# shield.net
KiCad netlist of a schematic drawn in EAGLE
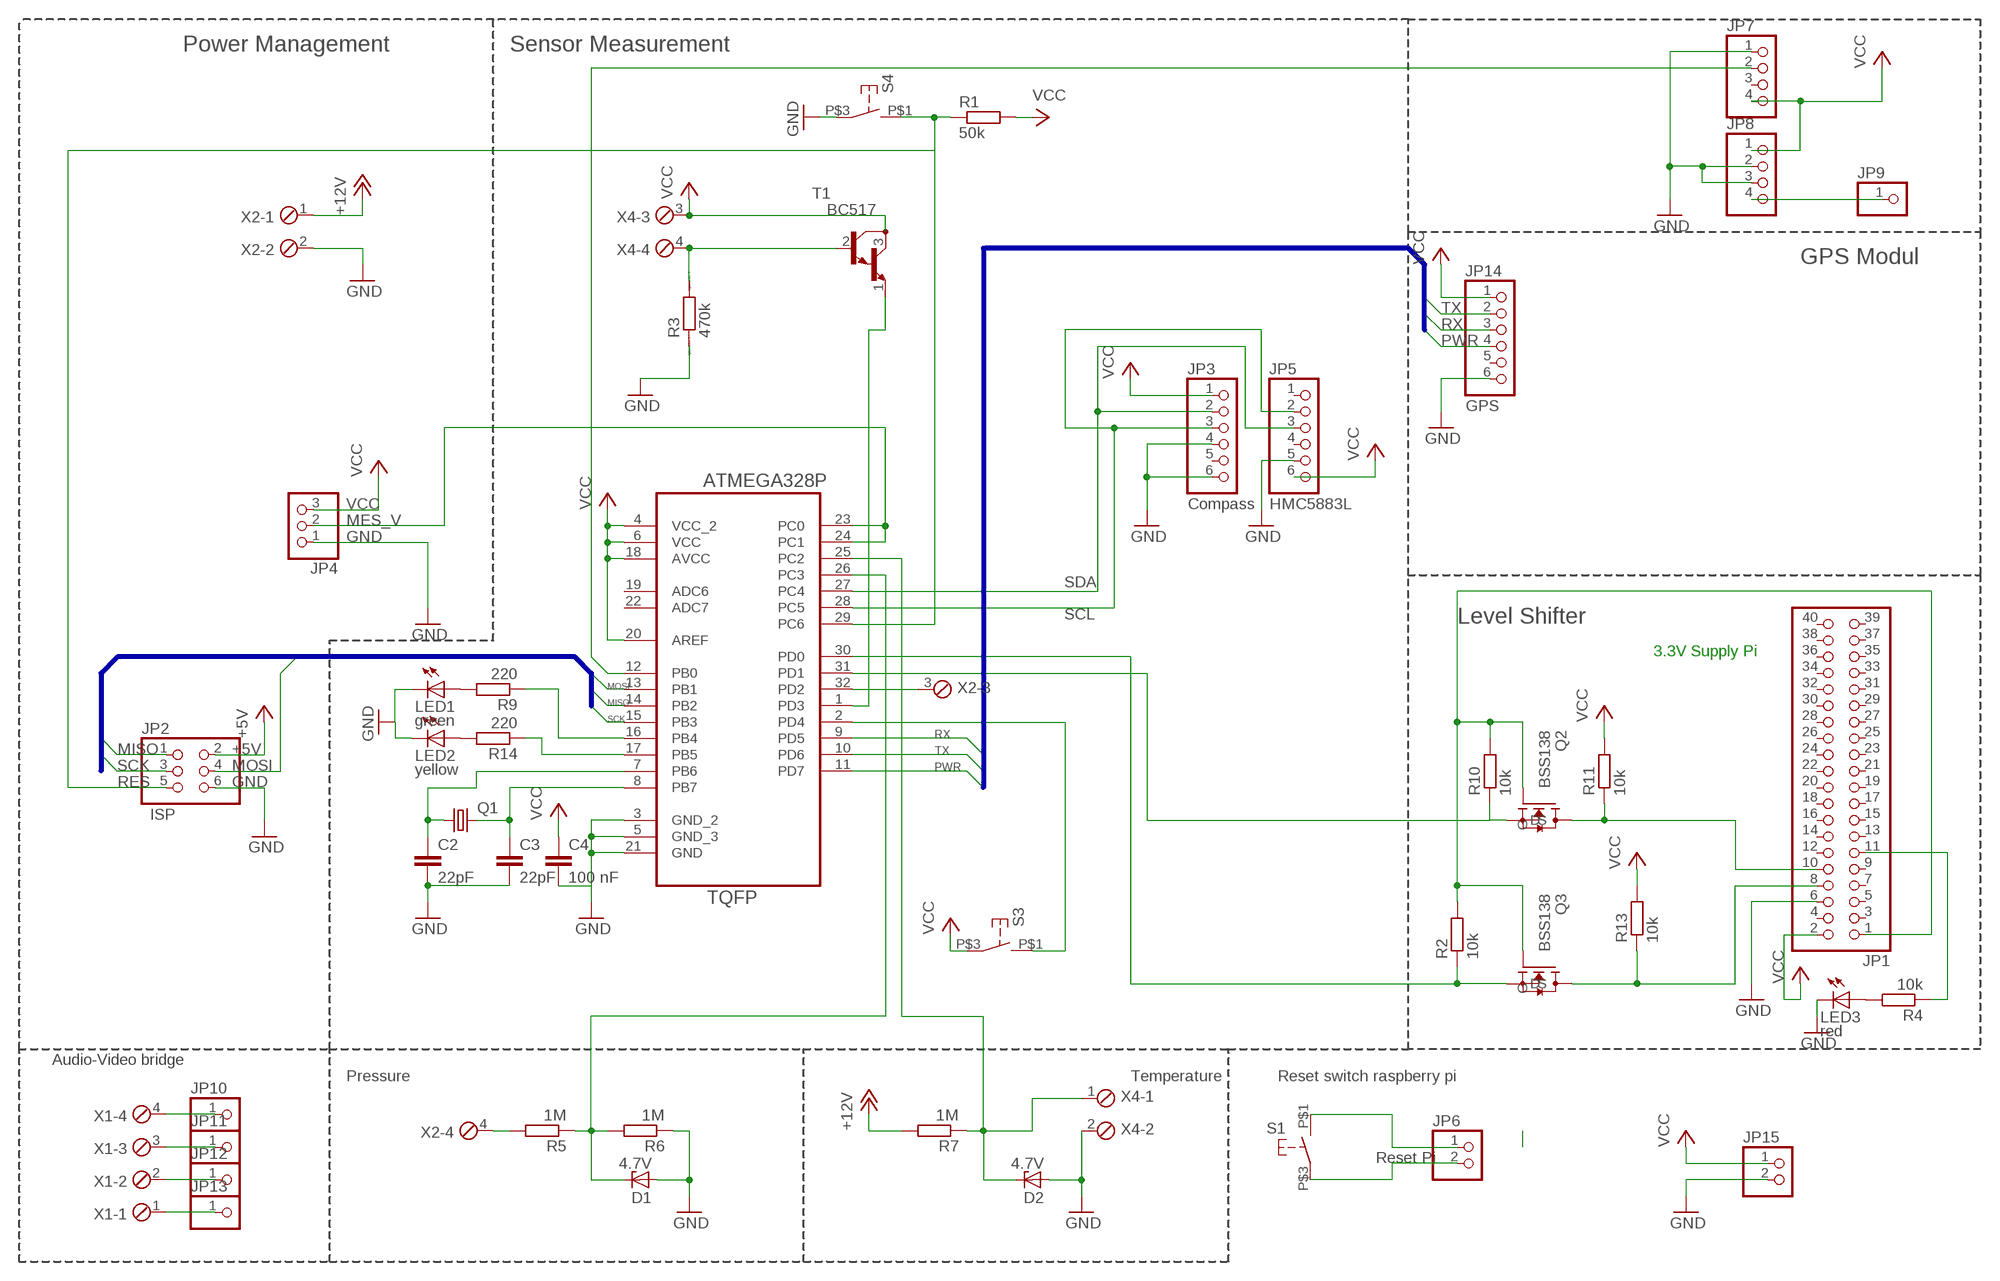
[diagram p0: schematic, sheet 1]

(export (version "E")
  (design (tool "Eeschema 10.0.6"))
  (components
    (comp (ref "C2")
      (value "22pF")
      (footprint "eagle-import:C1206")
      (libsource (lib "eagle-import") (part "C-EUC1206"))
    )
    (comp (ref "C3")
      (value "22pF")
      (footprint "eagle-import:C1206")
      (libsource (lib "eagle-import") (part "C-EUC1206"))
    )
    (comp (ref "C4")
      (value "100 nF")
      (footprint "eagle-import:C0603")
      (libsource (lib "eagle-import") (part "C-EUC0603"))
    )
    (comp (ref "D1")
      (value "4.7V")
      (footprint "eagle-import:SOT23")
      (libsource (lib "eagle-import") (part "ZENER-DIODESOT23"))
    )
    (comp (ref "D2")
      (value "4.7V")
      (footprint "eagle-import:SOT23")
      (libsource (lib "eagle-import") (part "ZENER-DIODESOT23"))
    )
    (comp (ref "IC1")
      (value "ATMEGA328P-AU")
      (footprint "eagle-import:QFP80P900X900X120-32N")
      (libsource (lib "eagle-import") (part "ATMEGA328P-AU"))
    )
    (comp (ref "JP1")
      (value "PINHD-2X20")
      (footprint "eagle-import:2X20")
      (libsource (lib "eagle-import") (part "PINHD-2X20"))
    )
    (comp (ref "JP2")
      (value "PINHD-2X3")
      (footprint "eagle-import:2X03")
      (libsource (lib "eagle-import") (part "PINHD-2X3"))
    )
    (comp (ref "JP3")
      (value "Compass")
      (footprint "eagle-import:1X06")
      (libsource (lib "eagle-import") (part "PINHD-1X6"))
    )
    (comp (ref "JP4")
      (value "PINHD-1X3")
      (footprint "eagle-import:1X03")
      (libsource (lib "eagle-import") (part "PINHD-1X3"))
    )
    (comp (ref "JP5")
      (value "HMC5883L")
      (footprint "eagle-import:1X06")
      (libsource (lib "eagle-import") (part "PINHD-1X6"))
    )
    (comp (ref "JP6")
      (value "PINHD-1X2")
      (footprint "eagle-import:1X02")
      (libsource (lib "eagle-import") (part "PINHD-1X2"))
    )
    (comp (ref "JP7")
      (value "PINHD-1X4")
      (footprint "eagle-import:1X04")
      (libsource (lib "eagle-import") (part "PINHD-1X4"))
    )
    (comp (ref "JP8")
      (value "PINHD-1X4")
      (footprint "eagle-import:1X04")
      (libsource (lib "eagle-import") (part "PINHD-1X4"))
    )
    (comp (ref "JP9")
      (value "PINHD-1X1")
      (footprint "eagle-import:1X01")
      (libsource (lib "eagle-import") (part "PINHD-1X1"))
    )
    (comp (ref "JP10")
      (value "PINHD-1X1")
      (footprint "eagle-import:1X01")
      (libsource (lib "eagle-import") (part "PINHD-1X1"))
    )
    (comp (ref "JP11")
      (value "PINHD-1X1")
      (footprint "eagle-import:1X01")
      (libsource (lib "eagle-import") (part "PINHD-1X1"))
    )
    (comp (ref "JP12")
      (value "PINHD-1X1")
      (footprint "eagle-import:1X01")
      (libsource (lib "eagle-import") (part "PINHD-1X1"))
    )
    (comp (ref "JP13")
      (value "PINHD-1X1")
      (footprint "eagle-import:1X01")
      (libsource (lib "eagle-import") (part "PINHD-1X1"))
    )
    (comp (ref "JP14")
      (value "GPS")
      (footprint "eagle-import:1X06")
      (libsource (lib "eagle-import") (part "PINHD-1X6"))
    )
    (comp (ref "JP15")
      (value "PINHD-1X2")
      (footprint "eagle-import:1X02")
      (libsource (lib "eagle-import") (part "PINHD-1X2"))
    )
    (comp (ref "LED1")
      (value "green")
      (footprint "eagle-import:LED3MM")
      (libsource (lib "eagle-import") (part "LED3MM"))
    )
    (comp (ref "LED2")
      (value "yellow")
      (footprint "eagle-import:LED3MM")
      (libsource (lib "eagle-import") (part "LED3MM"))
    )
    (comp (ref "LED3")
      (value "red")
      (footprint "eagle-import:LED3MM")
      (libsource (lib "eagle-import") (part "LED3MM"))
    )
    (comp (ref "Q1")
      (value "CRYSTALHC49UP")
      (footprint "eagle-import:HC49UP")
      (libsource (lib "eagle-import") (part "CRYSTALHC49UP"))
    )
    (comp (ref "Q2")
      (value "BSS138")
      (footprint "eagle-import:BSS138")
      (libsource (lib "eagle-import") (part "BSS138"))
    )
    (comp (ref "Q3")
      (value "BSS138")
      (footprint "eagle-import:BSS138")
      (libsource (lib "eagle-import") (part "BSS138"))
    )
    (comp (ref "R1")
      (value "50k")
      (footprint "eagle-import:R1206")
      (libsource (lib "eagle-import") (part "resistor_R-EU_R1206"))
    )
    (comp (ref "R2")
      (value "10k")
      (footprint "eagle-import:R1206")
      (libsource (lib "eagle-import") (part "resistor_R-EU_R1206"))
    )
    (comp (ref "R3")
      (value "470k")
      (footprint "eagle-import:R1206")
      (libsource (lib "eagle-import") (part "RR1206"))
    )
    (comp (ref "R4")
      (value "10k")
      (footprint "eagle-import:R1206")
      (libsource (lib "eagle-import") (part "resistor_R-EU_R1206"))
    )
    (comp (ref "R5")
      (value "1M")
      (footprint "eagle-import:R1206")
      (libsource (lib "eagle-import") (part "R-EU_R1206"))
    )
    (comp (ref "R6")
      (value "1M")
      (footprint "eagle-import:R1206")
      (libsource (lib "eagle-import") (part "R-EU_R1206"))
    )
    (comp (ref "R7")
      (value "1M")
      (footprint "eagle-import:R1206")
      (libsource (lib "eagle-import") (part "R-EU_R1206"))
    )
    (comp (ref "R9")
      (value "220")
      (footprint "eagle-import:R1206")
      (libsource (lib "eagle-import") (part "resistor_R-EU_R1206"))
    )
    (comp (ref "R10")
      (value "10k")
      (footprint "eagle-import:R1206")
      (libsource (lib "eagle-import") (part "resistor_R-EU_R1206"))
    )
    (comp (ref "R11")
      (value "10k")
      (footprint "eagle-import:R1206")
      (libsource (lib "eagle-import") (part "resistor_R-EU_R1206"))
    )
    (comp (ref "R13")
      (value "10k")
      (footprint "eagle-import:R1206")
      (libsource (lib "eagle-import") (part "resistor_R-EU_R1206"))
    )
    (comp (ref "R14")
      (value "220")
      (footprint "eagle-import:R1206")
      (libsource (lib "eagle-import") (part "resistor_R-EU_R1206"))
    )
    (comp (ref "S1")
      (value "SCHLIESSER_TASTSCHALTER")
      (footprint "eagle-import:NAMAE-JTP-1130")
      (libsource (lib "eagle-import") (part "SCHLIESSER_TASTSCHALTER"))
    )
    (comp (ref "S3")
      (value "SCHLIESSER_TASTSCHALTER")
      (footprint "eagle-import:NAMAE-JTP-1130")
      (libsource (lib "eagle-import") (part "SCHLIESSER_TASTSCHALTER"))
    )
    (comp (ref "S4")
      (value "SCHLIESSER_TASTSCHALTER")
      (footprint "eagle-import:NAMAE-JTP-1130")
      (libsource (lib "eagle-import") (part "SCHLIESSER_TASTSCHALTER"))
    )
    (comp (ref "T1")
      (value "BC517")
      (footprint "eagle-import:TO92")
      (libsource (lib "eagle-import") (part "BC517"))
    )
    (comp (ref "X1")
      (value "MPT4")
      (footprint "eagle-import:4POL254")
      (libsource (lib "eagle-import") (part "MPT4"))
    )
    (comp (ref "X2")
      (value "MPT4")
      (footprint "eagle-import:4POL254")
      (libsource (lib "eagle-import") (part "MPT4"))
    )
    (comp (ref "X4")
      (value "MPT4")
      (footprint "eagle-import:4POL254")
      (libsource (lib "eagle-import") (part "MPT4"))
    )
  )
  (nets
    (net (code "1") (name "+5V") (class "Default")
      (node (ref "JP2") (pin "2") (pinfunction "2_2") (pintype "passive"))
    )
    (net (code "2") (name "+12V") (class "Default")
      (node (ref "R7") (pin "2") (pinfunction "2_2") (pintype "passive"))
      (node (ref "X2") (pin "1") (pinfunction "1_1") (pintype "passive"))
    )
    (net (code "3") (name "/MES_V") (class "Default")
      (node (ref "IC1") (pin "23") (pinfunction "PC0_23") (pintype "bidirectional"))
      (node (ref "IC1") (pin "24") (pinfunction "PC1_24") (pintype "bidirectional"))
      (node (ref "JP4") (pin "2") (pinfunction "2_2") (pintype "passive"))
    )
    (net (code "4") (name "/MISO") (class "Default")
      (node (ref "IC1") (pin "14") (pinfunction "PB2_14") (pintype "bidirectional"))
      (node (ref "JP2") (pin "1") (pinfunction "1_1") (pintype "passive"))
    )
    (net (code "5") (name "/MOSI") (class "Default")
      (node (ref "IC1") (pin "13") (pinfunction "PB1_13") (pintype "bidirectional"))
      (node (ref "JP2") (pin "4") (pinfunction "4_4") (pintype "passive"))
    )
    (net (code "6") (name "/PWR") (class "Default")
      (node (ref "IC1") (pin "11") (pinfunction "PD7_11") (pintype "bidirectional"))
      (node (ref "JP14") (pin "4") (pinfunction "4_4") (pintype "passive"))
    )
    (net (code "7") (name "/RES") (class "Default")
      (node (ref "IC1") (pin "29") (pinfunction "PC6_29") (pintype "bidirectional"))
      (node (ref "JP2") (pin "5") (pinfunction "5_5") (pintype "passive"))
      (node (ref "R1") (pin "1") (pinfunction "1_1") (pintype "passive"))
      (node (ref "S4") (pin "P$1") (pinfunction "3_P$1") (pintype "input"))
    )
    (net (code "8") (name "/RX") (class "Default")
      (node (ref "IC1") (pin "9") (pinfunction "PD5_9") (pintype "bidirectional"))
      (node (ref "JP14") (pin "3") (pinfunction "3_3") (pintype "passive"))
    )
    (net (code "9") (name "/SCK") (class "Default")
      (node (ref "IC1") (pin "15") (pinfunction "PB3_15") (pintype "bidirectional"))
      (node (ref "JP2") (pin "3") (pinfunction "3_3") (pintype "passive"))
    )
    (net (code "10") (name "/TX") (class "Default")
      (node (ref "IC1") (pin "10") (pinfunction "PD6_10") (pintype "bidirectional"))
      (node (ref "JP14") (pin "2") (pinfunction "2_2") (pintype "passive"))
    )
    (net (code "11") (name "GND") (class "Default")
      (node (ref "C2") (pin "2") (pinfunction "2_2") (pintype "passive"))
      (node (ref "C3") (pin "2") (pinfunction "2_2") (pintype "passive"))
      (node (ref "C4") (pin "2") (pinfunction "2_2") (pintype "passive"))
      (node (ref "D1") (pin "1") (pinfunction "A_1") (pintype "passive"))
      (node (ref "D2") (pin "1") (pinfunction "A_1") (pintype "passive"))
      (node (ref "IC1") (pin "21") (pinfunction "GND_21") (pintype "passive"))
      (node (ref "IC1") (pin "3") (pinfunction "GND_2_3") (pintype "passive"))
      (node (ref "IC1") (pin "5") (pinfunction "GND_3_5") (pintype "passive"))
      (node (ref "JP1") (pin "6") (pinfunction "6_6") (pintype "passive"))
      (node (ref "JP14") (pin "6") (pinfunction "6_6") (pintype "passive"))
      (node (ref "JP15") (pin "2") (pinfunction "2_2") (pintype "passive"))
      (node (ref "JP2") (pin "6") (pinfunction "6_6") (pintype "passive"))
      (node (ref "JP3") (pin "4") (pinfunction "4_4") (pintype "passive"))
      (node (ref "JP3") (pin "6") (pinfunction "6_6") (pintype "passive"))
      (node (ref "JP4") (pin "1") (pinfunction "1_1") (pintype "passive"))
      (node (ref "JP5") (pin "5") (pinfunction "5_5") (pintype "passive"))
      (node (ref "JP7") (pin "1") (pinfunction "1_1") (pintype "passive"))
      (node (ref "JP8") (pin "2") (pinfunction "2_2") (pintype "passive"))
      (node (ref "JP8") (pin "3") (pinfunction "3_3") (pintype "passive"))
      (node (ref "LED1") (pin "K") (pinfunction "C_K") (pintype "passive"))
      (node (ref "LED2") (pin "K") (pinfunction "C_K") (pintype "passive"))
      (node (ref "LED3") (pin "K") (pinfunction "C_K") (pintype "passive"))
      (node (ref "R3") (pin "1") (pinfunction "1_1") (pintype "passive"))
      (node (ref "R6") (pin "1") (pinfunction "1_1") (pintype "passive"))
      (node (ref "S4") (pin "P$3") (pinfunction "4_P$3") (pintype "input"))
      (node (ref "X2") (pin "2") (pinfunction "1_2") (pintype "passive"))
      (node (ref "X4") (pin "2") (pinfunction "1_2") (pintype "passive"))
    )
    (net (code "12") (name "Net-(D1-C)") (class "Default")
      (node (ref "D1") (pin "3") (pinfunction "C_3") (pintype "passive"))
      (node (ref "IC1") (pin "26") (pinfunction "PC3_26") (pintype "bidirectional"))
      (node (ref "R5") (pin "1") (pinfunction "1_1") (pintype "passive"))
      (node (ref "R6") (pin "2") (pinfunction "2_2") (pintype "passive"))
    )
    (net (code "13") (name "Net-(D2-C)") (class "Default")
      (node (ref "D2") (pin "3") (pinfunction "C_3") (pintype "passive"))
      (node (ref "IC1") (pin "25") (pinfunction "PC2_25") (pintype "bidirectional"))
      (node (ref "R7") (pin "1") (pinfunction "1_1") (pintype "passive"))
      (node (ref "X4") (pin "1") (pinfunction "1_1") (pintype "passive"))
    )
    (net (code "14") (name "Net-(IC1-PB0)") (class "Default")
      (node (ref "IC1") (pin "12") (pinfunction "PB0_12") (pintype "bidirectional"))
      (node (ref "JP7") (pin "2") (pinfunction "2_2") (pintype "passive"))
    )
    (net (code "15") (name "Net-(IC1-PB4)") (class "Default")
      (node (ref "IC1") (pin "16") (pinfunction "PB4_16") (pintype "bidirectional"))
      (node (ref "R9") (pin "1") (pinfunction "1_1") (pintype "passive"))
    )
    (net (code "16") (name "Net-(IC1-PB5)") (class "Default")
      (node (ref "IC1") (pin "17") (pinfunction "PB5_17") (pintype "bidirectional"))
      (node (ref "R14") (pin "1") (pinfunction "1_1") (pintype "passive"))
    )
    (net (code "17") (name "Net-(IC1-PB6)") (class "Default")
      (node (ref "C2") (pin "1") (pinfunction "1_1") (pintype "passive"))
      (node (ref "IC1") (pin "7") (pinfunction "PB6_7") (pintype "bidirectional"))
      (node (ref "Q1") (pin "1") (pinfunction "1_1") (pintype "passive"))
    )
    (net (code "18") (name "Net-(IC1-PB7)") (class "Default")
      (node (ref "C3") (pin "1") (pinfunction "1_1") (pintype "passive"))
      (node (ref "IC1") (pin "8") (pinfunction "PB7_8") (pintype "bidirectional"))
      (node (ref "Q1") (pin "2") (pinfunction "2_2") (pintype "passive"))
    )
    (net (code "19") (name "Net-(IC1-PC4)") (class "Default")
      (node (ref "IC1") (pin "27") (pinfunction "PC4_27") (pintype "bidirectional"))
      (node (ref "JP3") (pin "2") (pinfunction "2_2") (pintype "passive"))
      (node (ref "JP5") (pin "3") (pinfunction "3_3") (pintype "passive"))
    )
    (net (code "20") (name "Net-(IC1-PC5)") (class "Default")
      (node (ref "IC1") (pin "28") (pinfunction "PC5_28") (pintype "bidirectional"))
      (node (ref "JP3") (pin "3") (pinfunction "3_3") (pintype "passive"))
      (node (ref "JP5") (pin "2") (pinfunction "2_2") (pintype "passive"))
    )
    (net (code "21") (name "Net-(IC1-PD0)") (class "Default")
      (node (ref "IC1") (pin "30") (pinfunction "PD0_30") (pintype "bidirectional"))
      (node (ref "Q3") (pin "S") (pinfunction "S_S") (pintype "passive"))
      (node (ref "R2") (pin "1") (pinfunction "1_1") (pintype "passive"))
    )
    (net (code "22") (name "Net-(IC1-PD1)") (class "Default")
      (node (ref "IC1") (pin "31") (pinfunction "PD1_31") (pintype "bidirectional"))
      (node (ref "Q2") (pin "S") (pinfunction "S_S") (pintype "passive"))
      (node (ref "R10") (pin "1") (pinfunction "1_1") (pintype "passive"))
    )
    (net (code "23") (name "Net-(IC1-PD2)") (class "Default")
      (node (ref "IC1") (pin "32") (pinfunction "PD2_32") (pintype "bidirectional"))
      (node (ref "X2") (pin "3") (pinfunction "1_3") (pintype "passive"))
    )
    (net (code "24") (name "Net-(IC1-PD3)") (class "Default")
      (node (ref "IC1") (pin "1") (pinfunction "PD3_1") (pintype "bidirectional"))
      (node (ref "T1") (pin "1") (pinfunction "E_1") (pintype "passive"))
    )
    (net (code "25") (name "Net-(IC1-PD4)") (class "Default")
      (node (ref "IC1") (pin "2") (pinfunction "PD4_2") (pintype "bidirectional"))
      (node (ref "S3") (pin "P$1") (pinfunction "3_P$1") (pintype "input"))
    )
    (net (code "26") (name "Net-(JP1-Pad1)") (class "Default")
      (node (ref "JP1") (pin "1") (pinfunction "1_1") (pintype "passive"))
      (node (ref "Q2") (pin "G") (pinfunction "G_G") (pintype "passive"))
      (node (ref "Q3") (pin "G") (pinfunction "G_G") (pintype "passive"))
      (node (ref "R10") (pin "2") (pinfunction "2_2") (pintype "passive"))
      (node (ref "R2") (pin "2") (pinfunction "2_2") (pintype "passive"))
    )
    (net (code "27") (name "Net-(JP1-Pad8)") (class "Default")
      (node (ref "JP1") (pin "8") (pinfunction "8_8") (pintype "passive"))
      (node (ref "Q3") (pin "D") (pinfunction "D_D") (pintype "passive"))
      (node (ref "R13") (pin "1") (pinfunction "1_1") (pintype "passive"))
    )
    (net (code "28") (name "Net-(JP1-Pad10)") (class "Default")
      (node (ref "JP1") (pin "10") (pinfunction "10_10") (pintype "passive"))
      (node (ref "Q2") (pin "D") (pinfunction "D_D") (pintype "passive"))
      (node (ref "R11") (pin "1") (pinfunction "1_1") (pintype "passive"))
    )
    (net (code "29") (name "Net-(JP1-Pad11)") (class "Default")
      (node (ref "JP1") (pin "11") (pinfunction "11_11") (pintype "passive"))
      (node (ref "R4") (pin "1") (pinfunction "1_1") (pintype "passive"))
    )
    (net (code "30") (name "Net-(JP8-Pad4)") (class "Default")
      (node (ref "JP8") (pin "4") (pinfunction "4_4") (pintype "passive"))
      (node (ref "JP9") (pin "1") (pinfunction "1_1") (pintype "passive"))
    )
    (net (code "31") (name "Net-(JP13-Pad1)") (class "Default")
      (node (ref "JP13") (pin "1") (pinfunction "1_1") (pintype "passive"))
      (node (ref "X1") (pin "1") (pinfunction "1_1") (pintype "passive"))
    )
    (net (code "32") (name "Net-(LED1-PadA)") (class "Default")
      (node (ref "LED1") (pin "A") (pinfunction "A_A") (pintype "passive"))
      (node (ref "R9") (pin "2") (pinfunction "2_2") (pintype "passive"))
    )
    (net (code "33") (name "Net-(LED2-PadA)") (class "Default")
      (node (ref "LED2") (pin "A") (pinfunction "A_A") (pintype "passive"))
      (node (ref "R14") (pin "2") (pinfunction "2_2") (pintype "passive"))
    )
    (net (code "34") (name "Net-(LED3-PadA)") (class "Default")
      (node (ref "LED3") (pin "A") (pinfunction "A_A") (pintype "passive"))
      (node (ref "R4") (pin "2") (pinfunction "2_2") (pintype "passive"))
    )
    (net (code "35") (name "Net-(S1-3)") (class "Default")
      (node (ref "JP6") (pin "1") (pinfunction "1_1") (pintype "passive"))
      (node (ref "S1") (pin "P$1") (pinfunction "3_P$1") (pintype "input"))
    )
    (net (code "36") (name "Net-(S1-4)") (class "Default")
      (node (ref "JP6") (pin "2") (pinfunction "2_2") (pintype "passive"))
      (node (ref "S1") (pin "P$3") (pinfunction "4_P$3") (pintype "input"))
    )
    (net (code "37") (name "Net-(T1-B)") (class "Default")
      (node (ref "R3") (pin "2") (pinfunction "2_2") (pintype "passive"))
      (node (ref "T1") (pin "2") (pinfunction "B_2") (pintype "passive"))
      (node (ref "X4") (pin "4") (pinfunction "1_4") (pintype "passive"))
    )
    (net (code "38") (name "Net-(X1B-1)") (class "Default")
      (node (ref "JP12") (pin "1") (pinfunction "1_1") (pintype "passive"))
      (node (ref "X1") (pin "2") (pinfunction "1_2") (pintype "passive"))
    )
    (net (code "39") (name "Net-(X1C-1)") (class "Default")
      (node (ref "JP11") (pin "1") (pinfunction "1_1") (pintype "passive"))
      (node (ref "X1") (pin "3") (pinfunction "1_3") (pintype "passive"))
    )
    (net (code "40") (name "Net-(X1D-1)") (class "Default")
      (node (ref "JP10") (pin "1") (pinfunction "1_1") (pintype "passive"))
      (node (ref "X1") (pin "4") (pinfunction "1_4") (pintype "passive"))
    )
    (net (code "41") (name "Net-(X2D-1)") (class "Default")
      (node (ref "R5") (pin "2") (pinfunction "2_2") (pintype "passive"))
      (node (ref "X2") (pin "4") (pinfunction "1_4") (pintype "passive"))
    )
    (net (code "42") (name "VCC") (class "Default")
      (node (ref "C4") (pin "1") (pinfunction "1_1") (pintype "passive"))
      (node (ref "IC1") (pin "18") (pinfunction "AVCC_18") (pintype "power_in"))
      (node (ref "IC1") (pin "20") (pinfunction "AREF_20") (pintype "input"))
      (node (ref "IC1") (pin "4") (pinfunction "VCC_2_4") (pintype "power_in"))
      (node (ref "IC1") (pin "6") (pinfunction "VCC_6") (pintype "power_in"))
      (node (ref "JP1") (pin "2") (pinfunction "2_2") (pintype "passive"))
      (node (ref "JP14") (pin "1") (pinfunction "1_1") (pintype "passive"))
      (node (ref "JP15") (pin "1") (pinfunction "1_1") (pintype "passive"))
      (node (ref "JP3") (pin "1") (pinfunction "1_1") (pintype "passive"))
      (node (ref "JP4") (pin "3") (pinfunction "3_3") (pintype "passive"))
      (node (ref "JP5") (pin "6") (pinfunction "6_6") (pintype "passive"))
      (node (ref "JP7") (pin "4") (pinfunction "4_4") (pintype "passive"))
      (node (ref "JP8") (pin "1") (pinfunction "1_1") (pintype "passive"))
      (node (ref "R1") (pin "2") (pinfunction "2_2") (pintype "passive"))
      (node (ref "R11") (pin "2") (pinfunction "2_2") (pintype "passive"))
      (node (ref "R13") (pin "2") (pinfunction "2_2") (pintype "passive"))
      (node (ref "S3") (pin "P$3") (pinfunction "4_P$3") (pintype "input"))
      (node (ref "T1") (pin "3") (pinfunction "C_3") (pintype "passive"))
      (node (ref "X4") (pin "3") (pinfunction "1_3") (pintype "passive"))
    )
    (net (code "43") (name "unconnected-(IC1-ADC6-Pad19)") (class "Default")
      (node (ref "IC1") (pin "19") (pinfunction "ADC6_19") (pintype "input"))
    )
    (net (code "44") (name "unconnected-(IC1-ADC7-Pad22)") (class "Default")
      (node (ref "IC1") (pin "22") (pinfunction "ADC7_22") (pintype "input"))
    )
    (net (code "45") (name "unconnected-(JP1-Pad3)") (class "Default")
      (node (ref "JP1") (pin "3") (pinfunction "3_3") (pintype "passive"))
    )
    (net (code "46") (name "unconnected-(JP1-Pad4)") (class "Default")
      (node (ref "JP1") (pin "4") (pinfunction "4_4") (pintype "passive"))
    )
    (net (code "47") (name "unconnected-(JP1-Pad5)") (class "Default")
      (node (ref "JP1") (pin "5") (pinfunction "5_5") (pintype "passive"))
    )
    (net (code "48") (name "unconnected-(JP1-Pad7)") (class "Default")
      (node (ref "JP1") (pin "7") (pinfunction "7_7") (pintype "passive"))
    )
    (net (code "49") (name "unconnected-(JP1-Pad9)") (class "Default")
      (node (ref "JP1") (pin "9") (pinfunction "9_9") (pintype "passive"))
    )
    (net (code "50") (name "unconnected-(JP1-Pad12)") (class "Default")
      (node (ref "JP1") (pin "12") (pinfunction "12_12") (pintype "passive"))
    )
    (net (code "51") (name "unconnected-(JP1-Pad13)") (class "Default")
      (node (ref "JP1") (pin "13") (pinfunction "13_13") (pintype "passive"))
    )
    (net (code "52") (name "unconnected-(JP1-Pad14)") (class "Default")
      (node (ref "JP1") (pin "14") (pinfunction "14_14") (pintype "passive"))
    )
    (net (code "53") (name "unconnected-(JP1-Pad15)") (class "Default")
      (node (ref "JP1") (pin "15") (pinfunction "15_15") (pintype "passive"))
    )
    (net (code "54") (name "unconnected-(JP1-Pad16)") (class "Default")
      (node (ref "JP1") (pin "16") (pinfunction "16_16") (pintype "passive"))
    )
    (net (code "55") (name "unconnected-(JP1-Pad17)") (class "Default")
      (node (ref "JP1") (pin "17") (pinfunction "17_17") (pintype "passive"))
    )
    (net (code "56") (name "unconnected-(JP1-Pad18)") (class "Default")
      (node (ref "JP1") (pin "18") (pinfunction "18_18") (pintype "passive"))
    )
    (net (code "57") (name "unconnected-(JP1-Pad19)") (class "Default")
      (node (ref "JP1") (pin "19") (pinfunction "19_19") (pintype "passive"))
    )
    (net (code "58") (name "unconnected-(JP1-Pad20)") (class "Default")
      (node (ref "JP1") (pin "20") (pinfunction "20_20") (pintype "passive"))
    )
    (net (code "59") (name "unconnected-(JP1-Pad21)") (class "Default")
      (node (ref "JP1") (pin "21") (pinfunction "21_21") (pintype "passive"))
    )
    (net (code "60") (name "unconnected-(JP1-Pad22)") (class "Default")
      (node (ref "JP1") (pin "22") (pinfunction "22_22") (pintype "passive"))
    )
    (net (code "61") (name "unconnected-(JP1-Pad23)") (class "Default")
      (node (ref "JP1") (pin "23") (pinfunction "23_23") (pintype "passive"))
    )
    (net (code "62") (name "unconnected-(JP1-Pad24)") (class "Default")
      (node (ref "JP1") (pin "24") (pinfunction "24_24") (pintype "passive"))
    )
    (net (code "63") (name "unconnected-(JP1-Pad25)") (class "Default")
      (node (ref "JP1") (pin "25") (pinfunction "25_25") (pintype "passive"))
    )
    (net (code "64") (name "unconnected-(JP1-Pad26)") (class "Default")
      (node (ref "JP1") (pin "26") (pinfunction "26_26") (pintype "passive"))
    )
    (net (code "65") (name "unconnected-(JP1-Pad27)") (class "Default")
      (node (ref "JP1") (pin "27") (pinfunction "27_27") (pintype "passive"))
    )
    (net (code "66") (name "unconnected-(JP1-Pad28)") (class "Default")
      (node (ref "JP1") (pin "28") (pinfunction "28_28") (pintype "passive"))
    )
    (net (code "67") (name "unconnected-(JP1-Pad29)") (class "Default")
      (node (ref "JP1") (pin "29") (pinfunction "29_29") (pintype "passive"))
    )
    (net (code "68") (name "unconnected-(JP1-Pad30)") (class "Default")
      (node (ref "JP1") (pin "30") (pinfunction "30_30") (pintype "passive"))
    )
    (net (code "69") (name "unconnected-(JP1-Pad31)") (class "Default")
      (node (ref "JP1") (pin "31") (pinfunction "31_31") (pintype "passive"))
    )
    (net (code "70") (name "unconnected-(JP1-Pad32)") (class "Default")
      (node (ref "JP1") (pin "32") (pinfunction "32_32") (pintype "passive"))
    )
    (net (code "71") (name "unconnected-(JP1-Pad33)") (class "Default")
      (node (ref "JP1") (pin "33") (pinfunction "33_33") (pintype "passive"))
    )
    (net (code "72") (name "unconnected-(JP1-Pad34)") (class "Default")
      (node (ref "JP1") (pin "34") (pinfunction "34_34") (pintype "passive"))
    )
    (net (code "73") (name "unconnected-(JP1-Pad35)") (class "Default")
      (node (ref "JP1") (pin "35") (pinfunction "35_35") (pintype "passive"))
    )
    (net (code "74") (name "unconnected-(JP1-Pad36)") (class "Default")
      (node (ref "JP1") (pin "36") (pinfunction "36_36") (pintype "passive"))
    )
    (net (code "75") (name "unconnected-(JP1-Pad37)") (class "Default")
      (node (ref "JP1") (pin "37") (pinfunction "37_37") (pintype "passive"))
    )
    (net (code "76") (name "unconnected-(JP1-Pad38)") (class "Default")
      (node (ref "JP1") (pin "38") (pinfunction "38_38") (pintype "passive"))
    )
    (net (code "77") (name "unconnected-(JP1-Pad39)") (class "Default")
      (node (ref "JP1") (pin "39") (pinfunction "39_39") (pintype "passive"))
    )
    (net (code "78") (name "unconnected-(JP1-Pad40)") (class "Default")
      (node (ref "JP1") (pin "40") (pinfunction "40_40") (pintype "passive"))
    )
    (net (code "79") (name "unconnected-(JP3-Pad5)") (class "Default")
      (node (ref "JP3") (pin "5") (pinfunction "5_5") (pintype "passive"))
    )
    (net (code "80") (name "unconnected-(JP5-Pad1)") (class "Default")
      (node (ref "JP5") (pin "1") (pinfunction "1_1") (pintype "passive"))
    )
    (net (code "81") (name "unconnected-(JP5-Pad4)") (class "Default")
      (node (ref "JP5") (pin "4") (pinfunction "4_4") (pintype "passive"))
    )
    (net (code "82") (name "unconnected-(JP7-Pad3)") (class "Default")
      (node (ref "JP7") (pin "3") (pinfunction "3_3") (pintype "passive"))
    )
    (net (code "83") (name "unconnected-(JP14-Pad5)") (class "Default")
      (node (ref "JP14") (pin "5") (pinfunction "5_5") (pintype "passive"))
    )
  )
)
